# RepCounter.net
KiCad netlist of a schematic drawn in Altium Designer
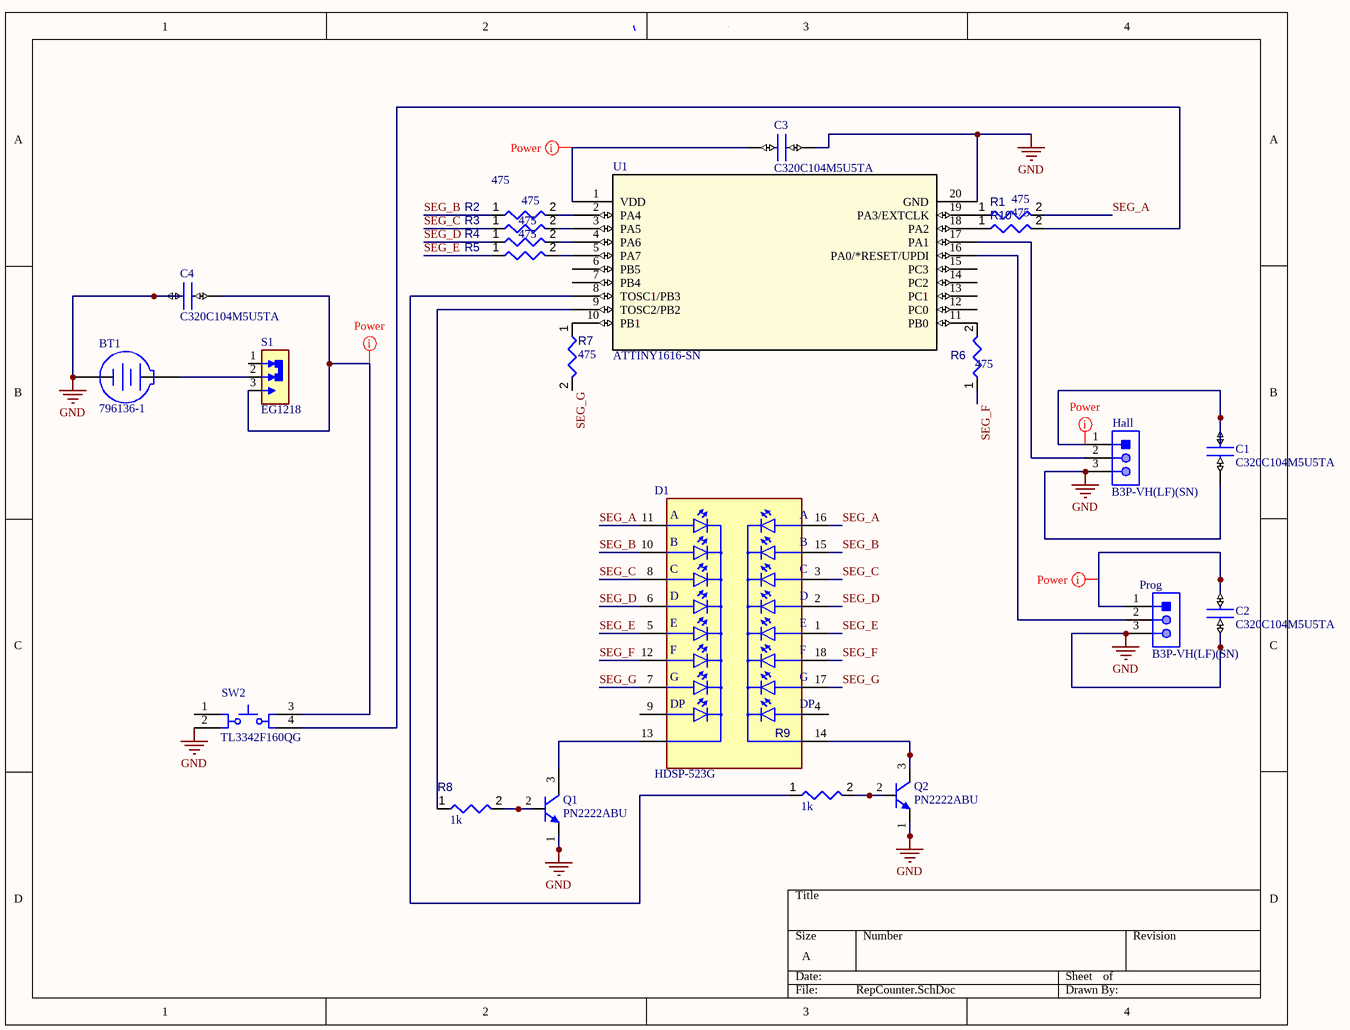
[diagram p0: RepCounter.SchDoc]

(export (version "E")
  (design (tool "Eeschema 10.0.6"))
  (components
    (comp (ref "BT1")
      (value "796136-1")
      (footprint "TECO-796136-1_V")
      (description "Battery Connector, 1 Cell, CR2032, 2-Pin SMD, RoHS, Tape and Reel")
      (fields (field (name "MANUFACTURER") "TE Connectivity"))
      (libsource (lib "Naiyar Malik") (part "BATTERY-HOLDER-COIN-2"))
    )
    (comp (ref "C1")
      (value "C320C104M5U5TA")
      (footprint "C320C")
      (fields (field (name "MF") "KEMET"))
      (libsource (lib "C320C104M5U5TA") (part "C320C104M5U5TA"))
    )
    (comp (ref "C2")
      (value "C320C104M5U5TA")
      (footprint "C320C")
      (fields (field (name "MF") "KEMET"))
      (libsource (lib "C320C104M5U5TA") (part "C320C104M5U5TA"))
    )
    (comp (ref "C3")
      (value "C320C104M5U5TA")
      (footprint "C320C")
      (fields (field (name "MF") "KEMET"))
      (libsource (lib "C320C104M5U5TA") (part "C320C104M5U5TA"))
    )
    (comp (ref "C4")
      (value "C320C104M5U5TA")
      (footprint "C320C")
      (fields (field (name "MF") "KEMET"))
      (libsource (lib "C320C104M5U5TA") (part "C320C104M5U5TA"))
    )
    (comp (ref "D1")
      (value "HDSP-523G")
      (footprint "LED_HDSP-523G")
      (description "Displays Segmented Panel 2DIGIT 16LED Green CC 18-Pin DIP Tube")
      (fields (field (name "MF") "Avago Technologies"))
      (libsource (lib "HDSP-523G") (part "HDSP-523G"))
    )
    (comp (ref "Hall")
      (value "B3P-VH(LF)(SN)")
      (footprint "JST-B3P-VH(LF)(SN)-3_V")
      (fields (field (name "MANUFACTURER") "JST"))
      (libsource (lib "Naiyar Malik") (part "CN-1P-M-R3"))
    )
    (comp (ref "Prog")
      (value "B3P-VH(LF)(SN)")
      (footprint "JST-B3P-VH(LF)(SN)-3_V")
      (fields (field (name "MANUFACTURER") "JST"))
      (libsource (lib "Naiyar Malik") (part "CN-1P-M-R3"))
    )
    (comp (ref "Q1")
      (value "PN2222ABU")
      (footprint "FAIR-TO-92")
      (description "NPN General-Purpose Amplifier, 40 V, -55 to 150 degC, 3-Pin TO-92, RoHS, Bulk")
      (fields (field (name "POWER") "625mW") (field (name "MANUFACTURER") "Fairchild"))
      (libsource (lib "Naiyar Malik") (part "BJT-NPN-EBC-3"))
    )
    (comp (ref "Q2")
      (value "PN2222ABU")
      (footprint "FAIR-TO-92")
      (description "NPN General-Purpose Amplifier, 40 V, -55 to 150 degC, 3-Pin TO-92, RoHS, Bulk")
      (fields (field (name "POWER") "625mW") (field (name "MANUFACTURER") "Fairchild"))
      (libsource (lib "Naiyar Malik") (part "BJT-NPN-EBC-3"))
    )
    (comp (ref "R1")
      (value "475")
      (footprint "RESA60-630X240")
      (description "Axial Resistor, 475 Ohm, +/- 1%, 0.25 W, -55 to 155 degC, 2-Pin THD, RoHS, Bulk")
      (fields (field (name "MANUFACTURER") "Yageo") (field (name "TOLERANCE") "1%"))
      (libsource (lib "Naiyar Malik") (part "RES-2"))
    )
    (comp (ref "R2")
      (value "475")
      (footprint "RESA60-630X240")
      (description "Axial Resistor, 475 Ohm, +/- 1%, 0.25 W, -55 to 155 degC, 2-Pin THD, RoHS, Bulk")
      (fields (field (name "MANUFACTURER") "Yageo") (field (name "TOLERANCE") "1%"))
      (libsource (lib "Naiyar Malik") (part "RES-2"))
    )
    (comp (ref "R3")
      (value "475")
      (footprint "RESA60-630X240")
      (description "Axial Resistor, 475 Ohm, +/- 1%, 0.25 W, -55 to 155 degC, 2-Pin THD, RoHS, Bulk")
      (fields (field (name "MANUFACTURER") "Yageo") (field (name "TOLERANCE") "1%"))
      (libsource (lib "Naiyar Malik") (part "RES-2"))
    )
    (comp (ref "R4")
      (value "475")
      (footprint "RESA60-630X240")
      (description "Axial Resistor, 475 Ohm, +/- 1%, 0.25 W, -55 to 155 degC, 2-Pin THD, RoHS, Bulk")
      (fields (field (name "MANUFACTURER") "Yageo") (field (name "TOLERANCE") "1%"))
      (libsource (lib "Naiyar Malik") (part "RES-2"))
    )
    (comp (ref "R5")
      (value "475")
      (footprint "RESA60-630X240")
      (description "Axial Resistor, 475 Ohm, +/- 1%, 0.25 W, -55 to 155 degC, 2-Pin THD, RoHS, Bulk")
      (fields (field (name "MANUFACTURER") "Yageo") (field (name "TOLERANCE") "1%"))
      (libsource (lib "Naiyar Malik") (part "RES-2"))
    )
    (comp (ref "R6")
      (value "475")
      (footprint "RESA60-630X240")
      (description "Axial Resistor, 475 Ohm, +/- 1%, 0.25 W, -55 to 155 degC, 2-Pin THD, RoHS, Bulk")
      (fields (field (name "MANUFACTURER") "Yageo") (field (name "TOLERANCE") "1%"))
      (libsource (lib "Naiyar Malik") (part "RES-2"))
    )
    (comp (ref "R7")
      (value "475")
      (footprint "RESA60-630X240")
      (description "Axial Resistor, 475 Ohm, +/- 1%, 0.25 W, -55 to 155 degC, 2-Pin THD, RoHS, Bulk")
      (fields (field (name "MANUFACTURER") "Yageo") (field (name "TOLERANCE") "1%"))
      (libsource (lib "Naiyar Malik") (part "RES-2"))
    )
    (comp (ref "R8")
      (value "1k")
      (footprint "RESA60-630X240")
      (description "Axial Resistor, 1 KOhm, +/- 1%, 250 mW, -55 to 155 degC, 2-Pin THD, RoHS, Bulk")
      (fields (field (name "TOLERANCE") "1%") (field (name "POWER") "250mW"))
      (libsource (lib "Naiyar Malik") (part "RES-2"))
    )
    (comp (ref "R9")
      (value "1k")
      (footprint "RESA60-630X240")
      (description "Axial Resistor, 1 KOhm, +/- 1%, 250 mW, -55 to 155 degC, 2-Pin THD, RoHS, Bulk")
      (fields (field (name "TOLERANCE") "1%") (field (name "POWER") "250mW"))
      (libsource (lib "Naiyar Malik") (part "RES-2"))
    )
    (comp (ref "R10")
      (value "475")
      (footprint "RESA60-630X240")
      (description "Axial Resistor, 475 Ohm, +/- 1%, 0.25 W, -55 to 155 degC, 2-Pin THD, RoHS, Bulk")
      (fields (field (name "MANUFACTURER") "Yageo") (field (name "TOLERANCE") "1%"))
      (libsource (lib "Naiyar Malik") (part "RES-2"))
    )
    (comp (ref "S1")
      (value "EG1218")
      (footprint "SW_EG1218")
      (description "Slide Switch, EG Series, SPDT, Non-Shorting, ON-ON, 200mA DC, 30VDC, PC Pin ¦ E-Switch EG1218")
      (fields (field (name "MF") "E-Switch"))
      (libsource (lib "EG1218") (part "EG1218"))
    )
    (comp (ref "SW2")
      (value "TL3342F160QG")
      (footprint "ESWI-TL3342F160QG_V")
      (description "Tactile Switch, SPST-NO, 50 mA, 12 V, 4-Pin SMD, RoHS, Tape and Reel")
      (fields (field (name "MANUFACTURER") "E-Switch"))
      (libsource (lib "Naiyar Malik") (part "SW-SPST-NO-4"))
    )
    (comp (ref "U1")
      (value "ATTINY1616-SN")
      (footprint "SOIC20_300MIL_MCH")
      (description "Description")
      (fields (field (name "COPYRIGHT") "Copyright (C) 2025 Ultra Librarian. All rights reserved."))
      (libsource (lib "ATTINY1616-SN") (part "ATTINY1616-SN"))
    )
  )
  (nets
    (net (code "1") (name "/SEG_A") (class "Default")
      (node (ref "D1") (pin "11") (pinfunction "A2_11") (pintype "passive"))
      (node (ref "D1") (pin "16") (pinfunction "A1_16") (pintype "passive"))
      (node (ref "R1") (pin "2") (pinfunction "2_2") (pintype "passive"))
    )
    (net (code "2") (name "/SEG_B") (class "Default")
      (node (ref "D1") (pin "10") (pinfunction "B2_10") (pintype "passive"))
      (node (ref "D1") (pin "15") (pinfunction "B1_15") (pintype "passive"))
      (node (ref "R2") (pin "1") (pinfunction "1_1") (pintype "passive"))
    )
    (net (code "3") (name "/SEG_C") (class "Default")
      (node (ref "D1") (pin "3") (pinfunction "C1_3") (pintype "passive"))
      (node (ref "D1") (pin "8") (pinfunction "C2_8") (pintype "passive"))
      (node (ref "R3") (pin "1") (pinfunction "1_1") (pintype "passive"))
    )
    (net (code "4") (name "/SEG_D") (class "Default")
      (node (ref "D1") (pin "2") (pinfunction "D1_2") (pintype "passive"))
      (node (ref "D1") (pin "6") (pinfunction "D2_6") (pintype "passive"))
      (node (ref "R4") (pin "1") (pinfunction "1_1") (pintype "passive"))
    )
    (net (code "5") (name "/SEG_E") (class "Default")
      (node (ref "D1") (pin "1") (pinfunction "E1_1") (pintype "passive"))
      (node (ref "D1") (pin "5") (pinfunction "E2_5") (pintype "passive"))
      (node (ref "R5") (pin "1") (pinfunction "1_1") (pintype "passive"))
    )
    (net (code "6") (name "/SEG_F") (class "Default")
      (node (ref "D1") (pin "12") (pinfunction "F2_12") (pintype "passive"))
      (node (ref "D1") (pin "18") (pinfunction "F1_18") (pintype "passive"))
      (node (ref "R6") (pin "1") (pinfunction "1_1") (pintype "passive"))
    )
    (net (code "7") (name "/SEG_G") (class "Default")
      (node (ref "D1") (pin "17") (pinfunction "G1_17") (pintype "passive"))
      (node (ref "D1") (pin "7") (pinfunction "G2_7") (pintype "passive"))
      (node (ref "R7") (pin "2") (pinfunction "2_2") (pintype "passive"))
    )
    (net (code "8") (name "GND") (class "Default")
      (node (ref "BT1") (pin "2") (pinfunction "-_2") (pintype "passive"))
      (node (ref "C1") (pin "2") (pinfunction "2_2") (pintype "bidirectional"))
      (node (ref "C2") (pin "2") (pinfunction "2_2") (pintype "bidirectional"))
      (node (ref "C3") (pin "2") (pinfunction "2_2") (pintype "bidirectional"))
      (node (ref "C4") (pin "1") (pinfunction "1_1") (pintype "bidirectional"))
      (node (ref "Hall") (pin "3") (pinfunction "3_3") (pintype "passive"))
      (node (ref "Prog") (pin "3") (pinfunction "3_3") (pintype "passive"))
      (node (ref "Q1") (pin "1") (pinfunction "E_1") (pintype "passive"))
      (node (ref "Q2") (pin "1") (pinfunction "E_1") (pintype "passive"))
      (node (ref "SW2") (pin "2") (pinfunction "2_2") (pintype "passive"))
      (node (ref "U1") (pin "20") (pinfunction "GND_20") (pintype "power_in"))
    )
    (net (code "9") (name "Net-(BT1-+)") (class "Default")
      (node (ref "BT1") (pin "1") (pinfunction "+_1") (pintype "passive"))
      (node (ref "S1") (pin "2") (pinfunction "COM_2") (pintype "passive"))
    )
    (net (code "10") (name "Net-(C1-Pad1)") (class "Default")
      (node (ref "C1") (pin "1") (pinfunction "1_1") (pintype "bidirectional"))
      (node (ref "Hall") (pin "1") (pinfunction "1_1") (pintype "passive"))
    )
    (net (code "11") (name "Net-(C2-Pad1)") (class "Default")
      (node (ref "C2") (pin "1") (pinfunction "1_1") (pintype "bidirectional"))
      (node (ref "Prog") (pin "1") (pinfunction "1_1") (pintype "passive"))
    )
    (net (code "12") (name "Net-(D1-COM1)") (class "Default")
      (node (ref "D1") (pin "14") (pinfunction "COM1_14") (pintype "passive"))
      (node (ref "Q2") (pin "3") (pinfunction "C_3") (pintype "passive"))
    )
    (net (code "13") (name "Net-(D1-COM2)") (class "Default")
      (node (ref "D1") (pin "13") (pinfunction "COM2_13") (pintype "passive"))
      (node (ref "Q1") (pin "3") (pinfunction "C_3") (pintype "passive"))
    )
    (net (code "14") (name "Net-(Q1-B)") (class "Default")
      (node (ref "Q1") (pin "2") (pinfunction "B_2") (pintype "passive"))
      (node (ref "R8") (pin "2") (pinfunction "2_2") (pintype "passive"))
    )
    (net (code "15") (name "Net-(Q2-B)") (class "Default")
      (node (ref "Q2") (pin "2") (pinfunction "B_2") (pintype "passive"))
      (node (ref "R9") (pin "2") (pinfunction "2_2") (pintype "passive"))
    )
    (net (code "16") (name "Net-(R10-Pad2)") (class "Default")
      (node (ref "R10") (pin "2") (pinfunction "2_2") (pintype "passive"))
      (node (ref "SW2") (pin "4") (pinfunction "4_4") (pintype "passive"))
    )
    (net (code "17") (name "Net-(S1-NO)") (class "Default")
      (node (ref "C4") (pin "2") (pinfunction "2_2") (pintype "bidirectional"))
      (node (ref "S1") (pin "3") (pinfunction "NO_3") (pintype "passive"))
      (node (ref "SW2") (pin "3") (pinfunction "3_3") (pintype "passive"))
    )
    (net (code "18") (name "Net-(U1-PA0{slash}*RESET{slash}UPDI)") (class "Default")
      (node (ref "Prog") (pin "2") (pinfunction "2_2") (pintype "passive"))
      (node (ref "U1") (pin "16") (pinfunction "PA0/*RESET/UPDI_16") (pintype "bidirectional"))
    )
    (net (code "19") (name "Net-(U1-PA1)") (class "Default")
      (node (ref "Hall") (pin "2") (pinfunction "2_2") (pintype "passive"))
      (node (ref "U1") (pin "17") (pinfunction "PA1_17") (pintype "bidirectional"))
    )
    (net (code "20") (name "Net-(U1-PA2)") (class "Default")
      (node (ref "R10") (pin "1") (pinfunction "1_1") (pintype "passive"))
      (node (ref "U1") (pin "18") (pinfunction "PA2_18") (pintype "bidirectional"))
    )
    (net (code "21") (name "Net-(U1-PA3{slash}EXTCLK)") (class "Default")
      (node (ref "R1") (pin "1") (pinfunction "1_1") (pintype "passive"))
      (node (ref "U1") (pin "19") (pinfunction "PA3/EXTCLK_19") (pintype "bidirectional"))
    )
    (net (code "22") (name "Net-(U1-PA4)") (class "Default")
      (node (ref "R2") (pin "2") (pinfunction "2_2") (pintype "passive"))
      (node (ref "U1") (pin "2") (pinfunction "PA4_2") (pintype "bidirectional"))
    )
    (net (code "23") (name "Net-(U1-PA5)") (class "Default")
      (node (ref "R3") (pin "2") (pinfunction "2_2") (pintype "passive"))
      (node (ref "U1") (pin "3") (pinfunction "PA5_3") (pintype "bidirectional"))
    )
    (net (code "24") (name "Net-(U1-PA6)") (class "Default")
      (node (ref "R4") (pin "2") (pinfunction "2_2") (pintype "passive"))
      (node (ref "U1") (pin "4") (pinfunction "PA6_4") (pintype "bidirectional"))
    )
    (net (code "25") (name "Net-(U1-PA7)") (class "Default")
      (node (ref "R5") (pin "2") (pinfunction "2_2") (pintype "passive"))
      (node (ref "U1") (pin "5") (pinfunction "PA7_5") (pintype "bidirectional"))
    )
    (net (code "26") (name "Net-(U1-PB0)") (class "Default")
      (node (ref "R6") (pin "2") (pinfunction "2_2") (pintype "passive"))
      (node (ref "U1") (pin "11") (pinfunction "PB0_11") (pintype "bidirectional"))
    )
    (net (code "27") (name "Net-(U1-PB1)") (class "Default")
      (node (ref "R7") (pin "1") (pinfunction "1_1") (pintype "passive"))
      (node (ref "U1") (pin "10") (pinfunction "PB1_10") (pintype "bidirectional"))
    )
    (net (code "28") (name "Net-(U1-TOSC1{slash}PB3)") (class "Default")
      (node (ref "R9") (pin "1") (pinfunction "1_1") (pintype "passive"))
      (node (ref "U1") (pin "8") (pinfunction "TOSC1/PB3_8") (pintype "bidirectional"))
    )
    (net (code "29") (name "Net-(U1-TOSC2{slash}PB2)") (class "Default")
      (node (ref "R8") (pin "1") (pinfunction "1_1") (pintype "passive"))
      (node (ref "U1") (pin "9") (pinfunction "TOSC2/PB2_9") (pintype "bidirectional"))
    )
    (net (code "30") (name "Net-(U1-VDD)") (class "Default")
      (node (ref "C3") (pin "1") (pinfunction "1_1") (pintype "bidirectional"))
      (node (ref "U1") (pin "1") (pinfunction "VDD_1") (pintype "power_in"))
    )
    (net (code "31") (name "unconnected-(D1-DP1-Pad4)") (class "Default")
      (node (ref "D1") (pin "4") (pinfunction "DP1_4") (pintype "passive"))
    )
    (net (code "32") (name "unconnected-(D1-DP2-Pad9)") (class "Default")
      (node (ref "D1") (pin "9") (pinfunction "DP2_9") (pintype "passive"))
    )
    (net (code "33") (name "unconnected-(S1-NC-Pad1)") (class "Default")
      (node (ref "S1") (pin "1") (pinfunction "NC_1") (pintype "passive"))
    )
    (net (code "34") (name "unconnected-(SW2-Pad1)") (class "Default")
      (node (ref "SW2") (pin "1") (pinfunction "1_1") (pintype "passive"))
    )
    (net (code "35") (name "unconnected-(U1-PB4-Pad7)") (class "Default")
      (node (ref "U1") (pin "7") (pinfunction "PB4_7") (pintype "bidirectional"))
    )
    (net (code "36") (name "unconnected-(U1-PB5-Pad6)") (class "Default")
      (node (ref "U1") (pin "6") (pinfunction "PB5_6") (pintype "bidirectional"))
    )
    (net (code "37") (name "unconnected-(U1-PC0-Pad12)") (class "Default")
      (node (ref "U1") (pin "12") (pinfunction "PC0_12") (pintype "bidirectional"))
    )
    (net (code "38") (name "unconnected-(U1-PC1-Pad13)") (class "Default")
      (node (ref "U1") (pin "13") (pinfunction "PC1_13") (pintype "bidirectional"))
    )
    (net (code "39") (name "unconnected-(U1-PC2-Pad14)") (class "Default")
      (node (ref "U1") (pin "14") (pinfunction "PC2_14") (pintype "bidirectional"))
    )
    (net (code "40") (name "unconnected-(U1-PC3-Pad15)") (class "Default")
      (node (ref "U1") (pin "15") (pinfunction "PC3_15") (pintype "bidirectional"))
    )
  )
)
